# Sheet1.net
KiCad netlist of a schematic drawn in Altium Designer
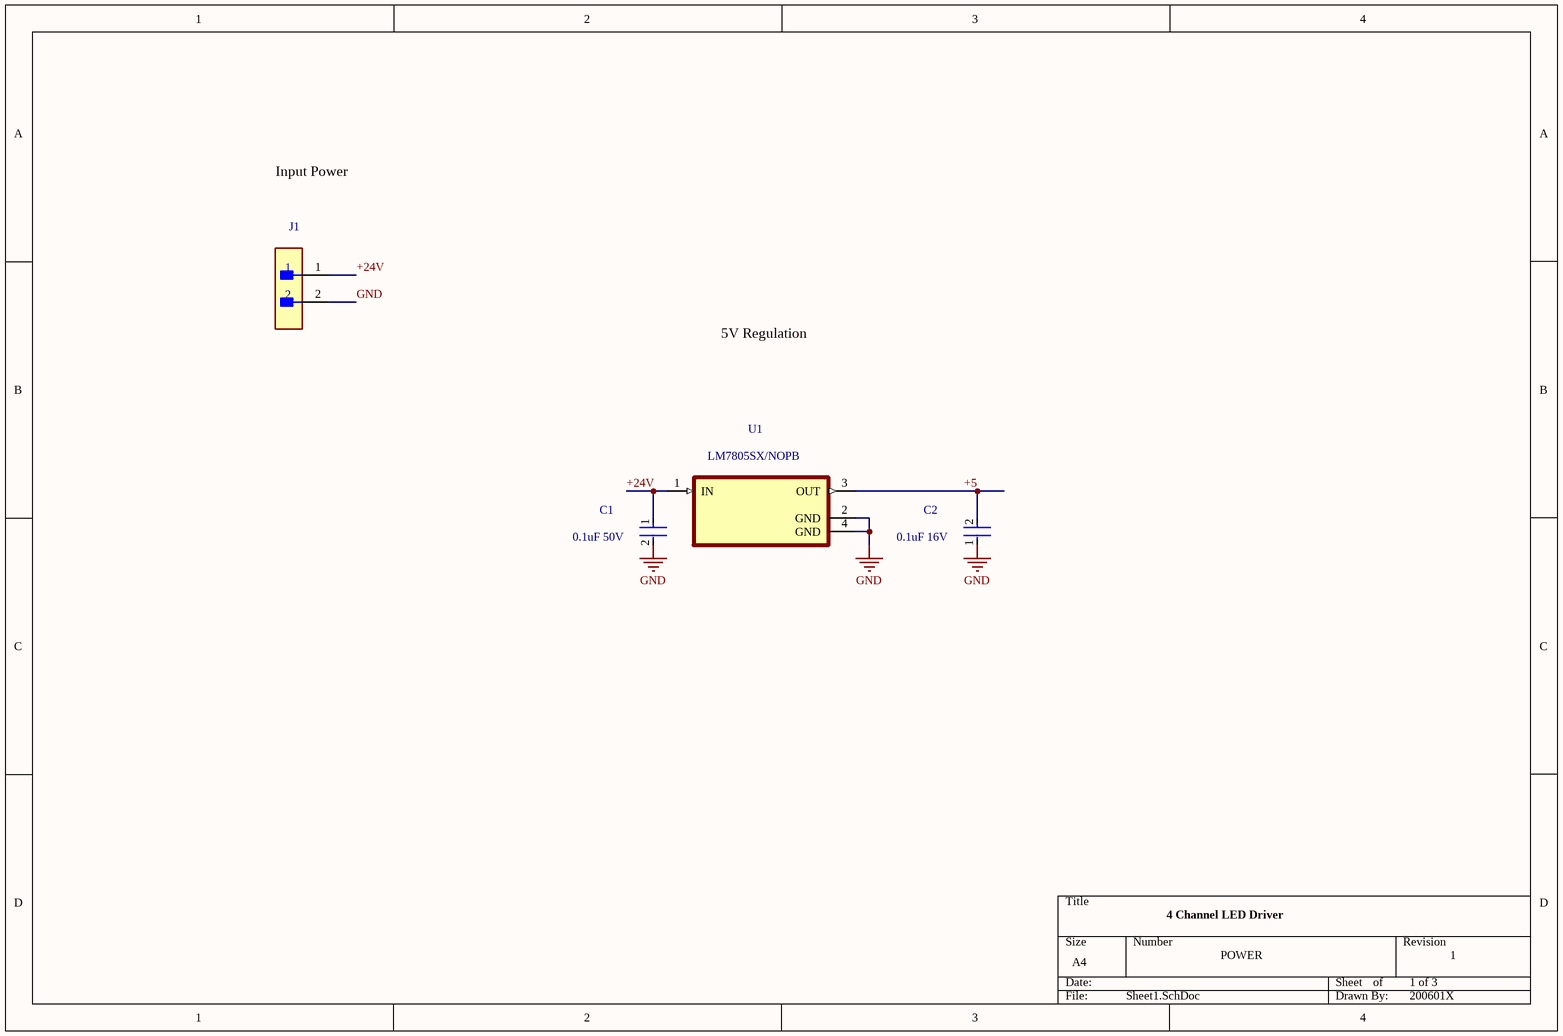
[diagram p0: Sheet1.SchDoc]

(export (version "E")
  (design (tool "Eeschema 10.0.6"))
  (components
    (comp (ref "C1")
      (value "0.1uF 50V")
      (footprint "FP-CL21-IPC_C")
      (description "CL21 Series 0805 100nF 50V ±10% Tolerance X7R Multilayer Ceramic Chip Capacitor")
      (fields (field (name "TOLERANCE") "10%") (field (name "VOLTAGE") "50V"))
      (libsource (lib "Altium Content Vault") (part "b4654b650e69147ec39a6b967a45e02"))
    )
    (comp (ref "C2")
      (value "0.1uF 16V")
      (footprint "FP-GRM15-MFG")
      (description "CAP CER 0.1UF 16V X7R 0402")
      (fields (field (name "MANUFACTURER PART NUMBER") "GRM155R71C104KA88D") (field (name "TOLERANCE") "10%"))
      (libsource (lib "Altium Content Vault") (part "236180d848d6139a670b325ea6854c9"))
    )
    (comp (ref "J1")
      (value "B2P-VH-FB-B(LF)(SN)")
      (footprint "FP-B2P-VH-FB-B_LF_SN-MFG")
      (description "CONN HEADER VERT 2POS 3.96MM")
      (libsource (lib "Altium Content Vault") (part "3bc925449376181038e59eaffc5286c"))
    )
    (comp (ref "U1")
      (value "LM7805SX/NOPB")
      (footprint "TO254P1524X483-4N")
      (description "1.5-A, 30-V, linear voltage regulator 3-DDPAK/TO-263 0 to 125")
      (fields (field (name "MF") "Texas Instruments"))
      (libsource (lib "LM7805SX_NOPB") (part "LM7805SX/NOPB"))
    )
  )
  (nets
    (net (code "1") (name "/+5") (class "Default")
      (node (ref "C2") (pin "2") (pinfunction "2_2") (pintype "passive"))
      (node (ref "U1") (pin "3") (pinfunction "OUT_3") (pintype "output"))
    )
    (net (code "2") (name "/+24V") (class "Default")
      (node (ref "C1") (pin "1") (pinfunction "1_1") (pintype "passive"))
      (node (ref "J1") (pin "1") (pinfunction "1_1") (pintype "passive"))
      (node (ref "U1") (pin "1") (pinfunction "IN_1") (pintype "input"))
    )
    (net (code "3") (name "GND") (class "Default")
      (node (ref "C1") (pin "2") (pinfunction "2_2") (pintype "passive"))
      (node (ref "C2") (pin "1") (pinfunction "1_1") (pintype "passive"))
      (node (ref "J1") (pin "2") (pinfunction "2_2") (pintype "passive"))
      (node (ref "U1") (pin "2") (pinfunction "GND_2") (pintype "power_in"))
      (node (ref "U1") (pin "4") (pinfunction "GND_4") (pintype "power_in"))
    )
  )
)
